# Sheet1.net
KiCad netlist of a schematic drawn in Altium Designer
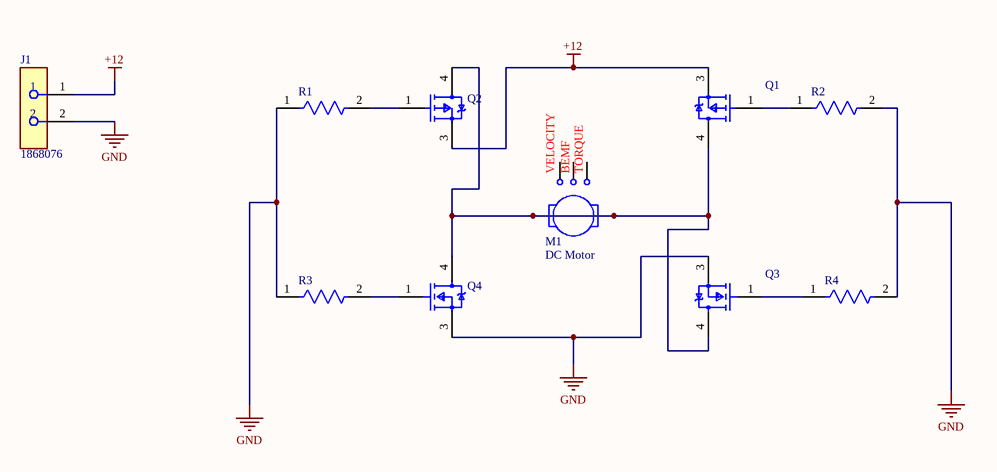
[diagram p0: Sheet1.SchDoc]

(export (version "E")
  (design (tool "Eeschema 10.0.6"))
  (components
    (comp (ref "J1")
      (value "1868076")
      (footprint "FP-1868076-MFG")
      (description "1868076 Conn Terminal Block 2 POS 7.62mm Solder ST Thru-Hole 32A Cardboard")
      (fields (field (name "VOLTAGE") "300V"))
      (libsource (lib "Altium Content Vault") (part "3ddab50f66188bb7952c54a1b76274c"))
    )
    (comp (ref "M1") (value "DC Motor") (libsource (lib "Simulation Generic Components") (part "DC Motor")))
    (comp (ref "Q1")
      (value "IRFR5410TRPBF")
      (footprint "FP-PG-TO252-3-MFG")
      (description "MOSFET P-CH 100V 13A DPAK")
      (fields
        (field (name "MANUFACTURER") "Infineon")
        (field (name "OCTOPART") "https://octopart.com/irfr5410trpbf-infineon-65874169")
      )
      (libsource (lib "Altium Content Vault") (part "84bd51c0c313388725e75e773aba525"))
    )
    (comp (ref "Q2")
      (value "IRFR5410TRPBF")
      (footprint "FP-PG-TO252-3-MFG")
      (description "MOSFET P-CH 100V 13A DPAK")
      (fields
        (field (name "MANUFACTURER") "Infineon")
        (field (name "OCTOPART") "https://octopart.com/irfr5410trpbf-infineon-65874169")
      )
      (libsource (lib "Altium Content Vault") (part "84bd51c0c313388725e75e773aba525"))
    )
    (comp (ref "Q3")
      (value "IRLZ44NSTRLPBF")
      (footprint "FP-PG-TO263-3-MFG")
      (description "MOSFET N-CH 55V 47A D2PAK")
      (libsource (lib "Altium Content Vault") (part "cdf1c68f84cb049e5ebc85739c3fcf6"))
    )
    (comp (ref "Q4")
      (value "IRLZ44NSTRLPBF")
      (footprint "FP-PG-TO263-3-MFG")
      (description "MOSFET N-CH 55V 47A D2PAK")
      (libsource (lib "Altium Content Vault") (part "cdf1c68f84cb049e5ebc85739c3fcf6"))
    )
    (comp (ref "R1")
      (value "MFR-25FBF52-1K18")
      (footprint "FP-MFR-25-MFG")
      (description "RES 1.18K OHM 1/4W 1% AXIAL")
      (fields (field (name "MANUFACTURER") "Yageo") (field (name "TOLERANCE") "1%"))
      (libsource (lib "Altium Content Vault") (part "1029c3af85768c4190bb7ad29bc67b5"))
    )
    (comp (ref "R2")
      (value "MFR-25FBF52-1K18")
      (footprint "FP-MFR-25-MFG")
      (description "RES 1.18K OHM 1/4W 1% AXIAL")
      (fields (field (name "MANUFACTURER") "Yageo") (field (name "TOLERANCE") "1%"))
      (libsource (lib "Altium Content Vault") (part "1029c3af85768c4190bb7ad29bc67b5"))
    )
    (comp (ref "R3")
      (value "MFR-25FBF52-1K18")
      (footprint "FP-MFR-25-MFG")
      (description "RES 1.18K OHM 1/4W 1% AXIAL")
      (fields (field (name "MANUFACTURER") "Yageo") (field (name "TOLERANCE") "1%"))
      (libsource (lib "Altium Content Vault") (part "1029c3af85768c4190bb7ad29bc67b5"))
    )
    (comp (ref "R4")
      (value "MFR-25FBF52-1K18")
      (footprint "FP-MFR-25-MFG")
      (description "RES 1.18K OHM 1/4W 1% AXIAL")
      (fields (field (name "MANUFACTURER") "Yageo") (field (name "TOLERANCE") "1%"))
      (libsource (lib "Altium Content Vault") (part "1029c3af85768c4190bb7ad29bc67b5"))
    )
  )
  (nets
    (net (code "1") (name "+12") (class "Default")
      (node (ref "J1") (pin "1") (pinfunction "1_1") (pintype "passive"))
      (node (ref "Q1") (pin "3") (pinfunction "S_3") (pintype "passive"))
      (node (ref "Q2") (pin "3") (pinfunction "S_3") (pintype "passive"))
    )
    (net (code "2") (name "GND") (class "Default")
      (node (ref "J1") (pin "2") (pinfunction "2_2") (pintype "passive"))
      (node (ref "Q3") (pin "3") (pinfunction "S_3") (pintype "passive"))
      (node (ref "Q4") (pin "3") (pinfunction "S_3") (pintype "passive"))
      (node (ref "R1") (pin "1") (pinfunction "1_1") (pintype "passive"))
      (node (ref "R2") (pin "2") (pinfunction "2_2") (pintype "passive"))
      (node (ref "R3") (pin "1") (pinfunction "1_1") (pintype "passive"))
      (node (ref "R4") (pin "2") (pinfunction "2_2") (pintype "passive"))
    )
    (net (code "3") (name "Net-(Q1-D)") (class "Default")
      (node (ref "M1") (pin "1") (pinfunction "1_1") (pintype "passive"))
      (node (ref "M1") (pin "2") (pinfunction "2_2") (pintype "passive"))
      (node (ref "Q1") (pin "4") (pinfunction "D_4") (pintype "passive"))
      (node (ref "Q2") (pin "4") (pinfunction "D_4") (pintype "passive"))
      (node (ref "Q3") (pin "4") (pinfunction "D_4") (pintype "passive"))
      (node (ref "Q4") (pin "4") (pinfunction "D_4") (pintype "passive"))
    )
    (net (code "4") (name "Net-(Q1-G)") (class "Default")
      (node (ref "Q1") (pin "1") (pinfunction "G_1") (pintype "passive"))
      (node (ref "R2") (pin "1") (pinfunction "1_1") (pintype "passive"))
    )
    (net (code "5") (name "Net-(Q2-G)") (class "Default")
      (node (ref "Q2") (pin "1") (pinfunction "G_1") (pintype "passive"))
      (node (ref "R1") (pin "2") (pinfunction "2_2") (pintype "passive"))
    )
    (net (code "6") (name "Net-(Q3-G)") (class "Default")
      (node (ref "Q3") (pin "1") (pinfunction "G_1") (pintype "passive"))
      (node (ref "R4") (pin "1") (pinfunction "1_1") (pintype "passive"))
    )
    (net (code "7") (name "Net-(Q4-G)") (class "Default")
      (node (ref "Q4") (pin "1") (pinfunction "G_1") (pintype "passive"))
      (node (ref "R3") (pin "2") (pinfunction "2_2") (pintype "passive"))
    )
    (net (code "8") (name "unconnected-(M1-Pad3)") (class "Default")
      (node (ref "M1") (pin "3") (pinfunction "3_3") (pintype "passive"))
    )
    (net (code "9") (name "unconnected-(M1-Pad4)") (class "Default")
      (node (ref "M1") (pin "4") (pinfunction "4_4") (pintype "passive"))
    )
    (net (code "10") (name "unconnected-(M1-Pad5)") (class "Default")
      (node (ref "M1") (pin "5") (pinfunction "5_5") (pintype "passive"))
    )
  )
)
